# adc_oscillator.net
KiCad netlist of a schematic drawn in Altium Designer
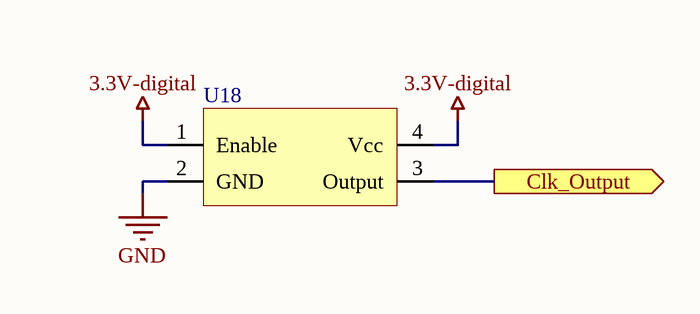
[diagram p0: adc_oscillator.SchDoc]

(export (version "E")
  (design (tool "Eeschema 10.0.6"))
  (components
    (comp (ref "U18")
      (value "Ceramic Crystal")
      (footprint "2.0 x 2.5 mm")
      (description "Ceramic Crystal 1 MHz, A-Grade 25 ppm/deg")
      (libsource (lib "GG") (part "ISM95-3251AH1.0000"))
    )
  )
  (nets
    (net (code "1") (name "/Clk_Output") (class "Default")
      (node (ref "U18") (pin "3") (pinfunction "Output_3") (pintype "passive"))
    )
    (net (code "2") (name "3.3V-digital") (class "Default")
      (node (ref "U18") (pin "1") (pinfunction "Enable_1") (pintype "passive"))
      (node (ref "U18") (pin "4") (pinfunction "Vcc_4") (pintype "passive"))
    )
    (net (code "3") (name "GND") (class "Default")
      (node (ref "U18") (pin "2") (pinfunction "GND_2") (pintype "passive"))
    )
  )
)
